# BMS_Carrier_-_Fan_Controls.net
KiCad netlist of a schematic drawn in Altium Designer
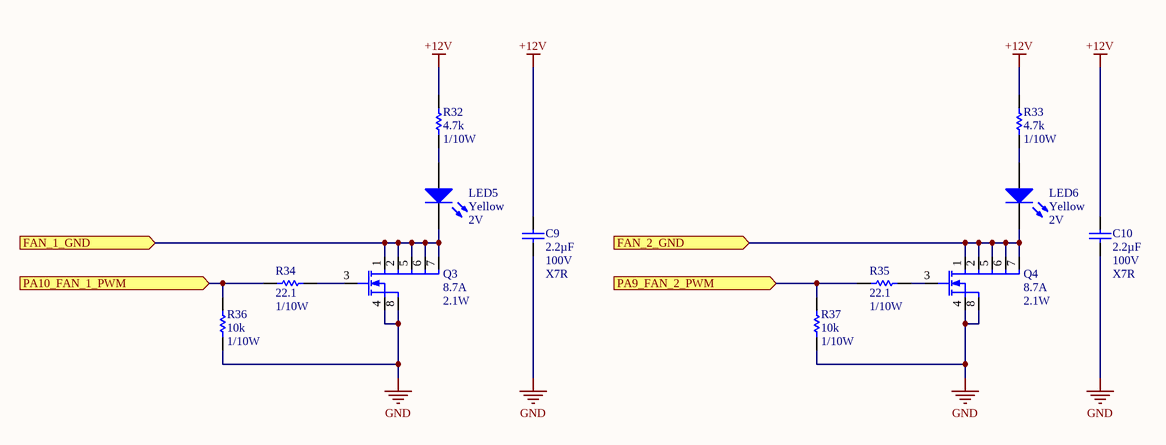
[diagram p0: BMS Carrier - Fan Controls.SchDoc]

(export (version "E")
  (design (tool "Eeschema 10.0.6"))
  (components
    (comp (ref "C9")
      (value "CAP CER 2.2UF 100V ±20% X7R 1206")
      (footprint "CAP, 1206")
      (description "2.2µF ±20% 100V Ceramic Capacitor X7R 1206 (3216 Metric)")
      (fields
        (field (name "TOLERANCE") "±20%")
        (field (name "CAPACITANCE") "2.2µF")
        (field (name "VOLTAGE") "100V")
        (field (name "TEMPERATURE COEFFICIENT") "X7R")
      )
      (libsource (lib "Schematic Diagrams") (part "CAP CER 2.2UF 100V ±20% X7R 1206"))
    )
    (comp (ref "C10")
      (value "CAP CER 2.2UF 100V ±20% X7R 1206")
      (footprint "CAP, 1206")
      (description "2.2µF ±20% 100V Ceramic Capacitor X7R 1206 (3216 Metric)")
      (fields
        (field (name "TOLERANCE") "±20%")
        (field (name "CAPACITANCE") "2.2µF")
        (field (name "VOLTAGE") "100V")
        (field (name "TEMPERATURE COEFFICIENT") "X7R")
      )
      (libsource (lib "Schematic Diagrams") (part "CAP CER 2.2UF 100V ±20% X7R 1206"))
    )
    (comp (ref "LED5")
      (value "LED YELLOW CLEAR 2.1V 0603")
      (footprint "LED_0603")
      (description "Yellow 590nm LED Indication - Discrete 2V 0603 (1608 Metric)")
      (fields
        (field (name "MANUFACTURER") "Wurth Electronics Inc.")
        (field (name "MANUFACTURER PART NUMBER") "150060YS75000")
        (field (name "COLOR") "Yellow")
        (field (name "VOLTAGE - FORWARD (VF) (TYP)") "2V")
      )
      (libsource (lib "Schematic Diagrams") (part "LED YELLOW CLEAR 2.1V 0603"))
    )
    (comp (ref "LED6")
      (value "LED YELLOW CLEAR 2.1V 0603")
      (footprint "LED_0603")
      (description "Yellow 590nm LED Indication - Discrete 2V 0603 (1608 Metric)")
      (fields
        (field (name "MANUFACTURER") "Wurth Electronics Inc.")
        (field (name "MANUFACTURER PART NUMBER") "150060YS75000")
        (field (name "COLOR") "Yellow")
        (field (name "VOLTAGE - FORWARD (VF) (TYP)") "2V")
      )
      (libsource (lib "Schematic Diagrams") (part "LED YELLOW CLEAR 2.1V 0603"))
    )
    (comp (ref "Q3")
      (value "MOSFET N-CH 30V 8.7A 2.1W 6-PQFN (2x2)")
      (footprint "MOSFET N-CH 30V 12A 2mmx2mm PQFN")
      (fields
        (field (name "CURRENT - CONTINUOUS DRAIN (ID) @ 25°C") "8.7A")
        (field (name "POWER DISSIPATION (MAX)") "2.1W")
      )
      (libsource (lib "Schematic Diagrams") (part "MOSFET N-CH 30V 8.7A 2.1W 6-PQFN (2x2)"))
    )
    (comp (ref "Q4")
      (value "MOSFET N-CH 30V 8.7A 2.1W 6-PQFN (2x2)")
      (footprint "MOSFET N-CH 30V 12A 2mmx2mm PQFN")
      (fields
        (field (name "CURRENT - CONTINUOUS DRAIN (ID) @ 25°C") "8.7A")
        (field (name "POWER DISSIPATION (MAX)") "2.1W")
      )
      (libsource (lib "Schematic Diagrams") (part "MOSFET N-CH 30V 8.7A 2.1W 6-PQFN (2x2)"))
    )
    (comp (ref "R32")
      (value "RES 4.7K OHM 1% 1/10W 0603")
      (footprint "RES, 0603")
      (description "4.7k Ohm ±1% 0.1W, 1/10W Chip Resistor 0603 (1608 Metric) Moisture Resistant Thick Film")
      (fields
        (field (name "TOLERANCE") "±1%")
        (field (name "RESISTANCE (OHMS)") "4.7k")
        (field (name "POWER (WATTS)") "1/10W")
      )
      (libsource (lib "Schematic Diagrams") (part "RES 4.7K OHM 1% 1/10W 0603"))
    )
    (comp (ref "R33")
      (value "RES 4.7K OHM 1% 1/10W 0603")
      (footprint "RES, 0603")
      (description "4.7k Ohm ±1% 0.1W, 1/10W Chip Resistor 0603 (1608 Metric) Moisture Resistant Thick Film")
      (fields
        (field (name "TOLERANCE") "±1%")
        (field (name "RESISTANCE (OHMS)") "4.7k")
        (field (name "POWER (WATTS)") "1/10W")
      )
      (libsource (lib "Schematic Diagrams") (part "RES 4.7K OHM 1% 1/10W 0603"))
    )
    (comp (ref "R34")
      (value "RES 22.1 OHM 1% 1/10W 0603")
      (footprint "RES, 0603")
      (description "22.1 Ohm ±1% 0.1W, 1/10W Chip Resistor 0603 (1608 Metric) Moisture Resistant Thick Film")
      (fields
        (field (name "TOLERANCE") "±1%")
        (field (name "RESISTANCE") "22.1")
        (field (name "POWER") "1/10W")
      )
      (libsource (lib "Schematic Diagrams") (part "RES 22.1 OHM 1% 1/10W 0603"))
    )
    (comp (ref "R35")
      (value "RES 22.1 OHM 1% 1/10W 0603")
      (footprint "RES, 0603")
      (description "22.1 Ohm ±1% 0.1W, 1/10W Chip Resistor 0603 (1608 Metric) Moisture Resistant Thick Film")
      (fields
        (field (name "TOLERANCE") "±1%")
        (field (name "RESISTANCE") "22.1")
        (field (name "POWER") "1/10W")
      )
      (libsource (lib "Schematic Diagrams") (part "RES 22.1 OHM 1% 1/10W 0603"))
    )
    (comp (ref "R36")
      (value "RES 10K OHM 1% 1/10W 0603")
      (footprint "RES, 0603")
      (description "RES SMD 10K OHM 1% 1/10W 0603")
      (fields
        (field (name "TOLERANCE") "±1%")
        (field (name "RESISTANCE") "10k")
        (field (name "POWER") "1/10W")
      )
      (libsource (lib "Schematic Diagrams") (part "RES 10K OHM 1% 1/10W 0603"))
    )
    (comp (ref "R37")
      (value "RES 10K OHM 1% 1/10W 0603")
      (footprint "RES, 0603")
      (description "RES SMD 10K OHM 1% 1/10W 0603")
      (fields
        (field (name "TOLERANCE") "±1%")
        (field (name "RESISTANCE") "10k")
        (field (name "POWER") "1/10W")
      )
      (libsource (lib "Schematic Diagrams") (part "RES 10K OHM 1% 1/10W 0603"))
    )
  )
  (nets
    (net (code "1") (name "+12V") (class "Default")
      (node (ref "C10") (pin "1") (pinfunction "1_1") (pintype "passive"))
      (node (ref "C9") (pin "1") (pinfunction "1_1") (pintype "passive"))
      (node (ref "R32") (pin "1") (pinfunction "1_1") (pintype "passive"))
      (node (ref "R33") (pin "1") (pinfunction "1_1") (pintype "passive"))
    )
    (net (code "2") (name "/FAN_1_GND") (class "Default")
      (node (ref "LED5") (pin "2") (pinfunction "K_2") (pintype "passive"))
      (node (ref "Q3") (pin "1") (pinfunction "D_1") (pintype "passive"))
      (node (ref "Q3") (pin "2") (pinfunction "D_2") (pintype "passive"))
      (node (ref "Q3") (pin "5") (pinfunction "D_5") (pintype "passive"))
      (node (ref "Q3") (pin "6") (pinfunction "D_6") (pintype "passive"))
      (node (ref "Q3") (pin "7") (pinfunction "D_7") (pintype "passive"))
    )
    (net (code "3") (name "/FAN_2_GND") (class "Default")
      (node (ref "LED6") (pin "2") (pinfunction "K_2") (pintype "passive"))
      (node (ref "Q4") (pin "1") (pinfunction "D_1") (pintype "passive"))
      (node (ref "Q4") (pin "2") (pinfunction "D_2") (pintype "passive"))
      (node (ref "Q4") (pin "5") (pinfunction "D_5") (pintype "passive"))
      (node (ref "Q4") (pin "6") (pinfunction "D_6") (pintype "passive"))
      (node (ref "Q4") (pin "7") (pinfunction "D_7") (pintype "passive"))
    )
    (net (code "4") (name "/PA9_FAN_2_PWM") (class "Default")
      (node (ref "R35") (pin "2") (pinfunction "2_2") (pintype "passive"))
      (node (ref "R37") (pin "1") (pinfunction "1_1") (pintype "passive"))
    )
    (net (code "5") (name "/PA10_FAN_1_PWM") (class "Default")
      (node (ref "R34") (pin "2") (pinfunction "2_2") (pintype "passive"))
      (node (ref "R36") (pin "1") (pinfunction "1_1") (pintype "passive"))
    )
    (net (code "6") (name "GND") (class "Default")
      (node (ref "C10") (pin "2") (pinfunction "2_2") (pintype "passive"))
      (node (ref "C9") (pin "2") (pinfunction "2_2") (pintype "passive"))
      (node (ref "Q3") (pin "4") (pinfunction "S_4") (pintype "passive"))
      (node (ref "Q3") (pin "8") (pinfunction "S_8") (pintype "passive"))
      (node (ref "Q4") (pin "4") (pinfunction "S_4") (pintype "passive"))
      (node (ref "Q4") (pin "8") (pinfunction "S_8") (pintype "passive"))
      (node (ref "R36") (pin "2") (pinfunction "2_2") (pintype "passive"))
      (node (ref "R37") (pin "2") (pinfunction "2_2") (pintype "passive"))
    )
    (net (code "7") (name "Net-(LED5-A)") (class "Default")
      (node (ref "LED5") (pin "1") (pinfunction "A_1") (pintype "passive"))
      (node (ref "R32") (pin "2") (pinfunction "2_2") (pintype "passive"))
    )
    (net (code "8") (name "Net-(LED6-A)") (class "Default")
      (node (ref "LED6") (pin "1") (pinfunction "A_1") (pintype "passive"))
      (node (ref "R33") (pin "2") (pinfunction "2_2") (pintype "passive"))
    )
    (net (code "9") (name "Net-(Q3-G)") (class "Default")
      (node (ref "Q3") (pin "3") (pinfunction "G_3") (pintype "passive"))
      (node (ref "R34") (pin "1") (pinfunction "1_1") (pintype "passive"))
    )
    (net (code "10") (name "Net-(Q4-G)") (class "Default")
      (node (ref "Q4") (pin "3") (pinfunction "G_3") (pintype "passive"))
      (node (ref "R35") (pin "1") (pinfunction "1_1") (pintype "passive"))
    )
  )
)
